# stknx_breakout.net
KiCad netlist of a schematic drawn in EAGLE
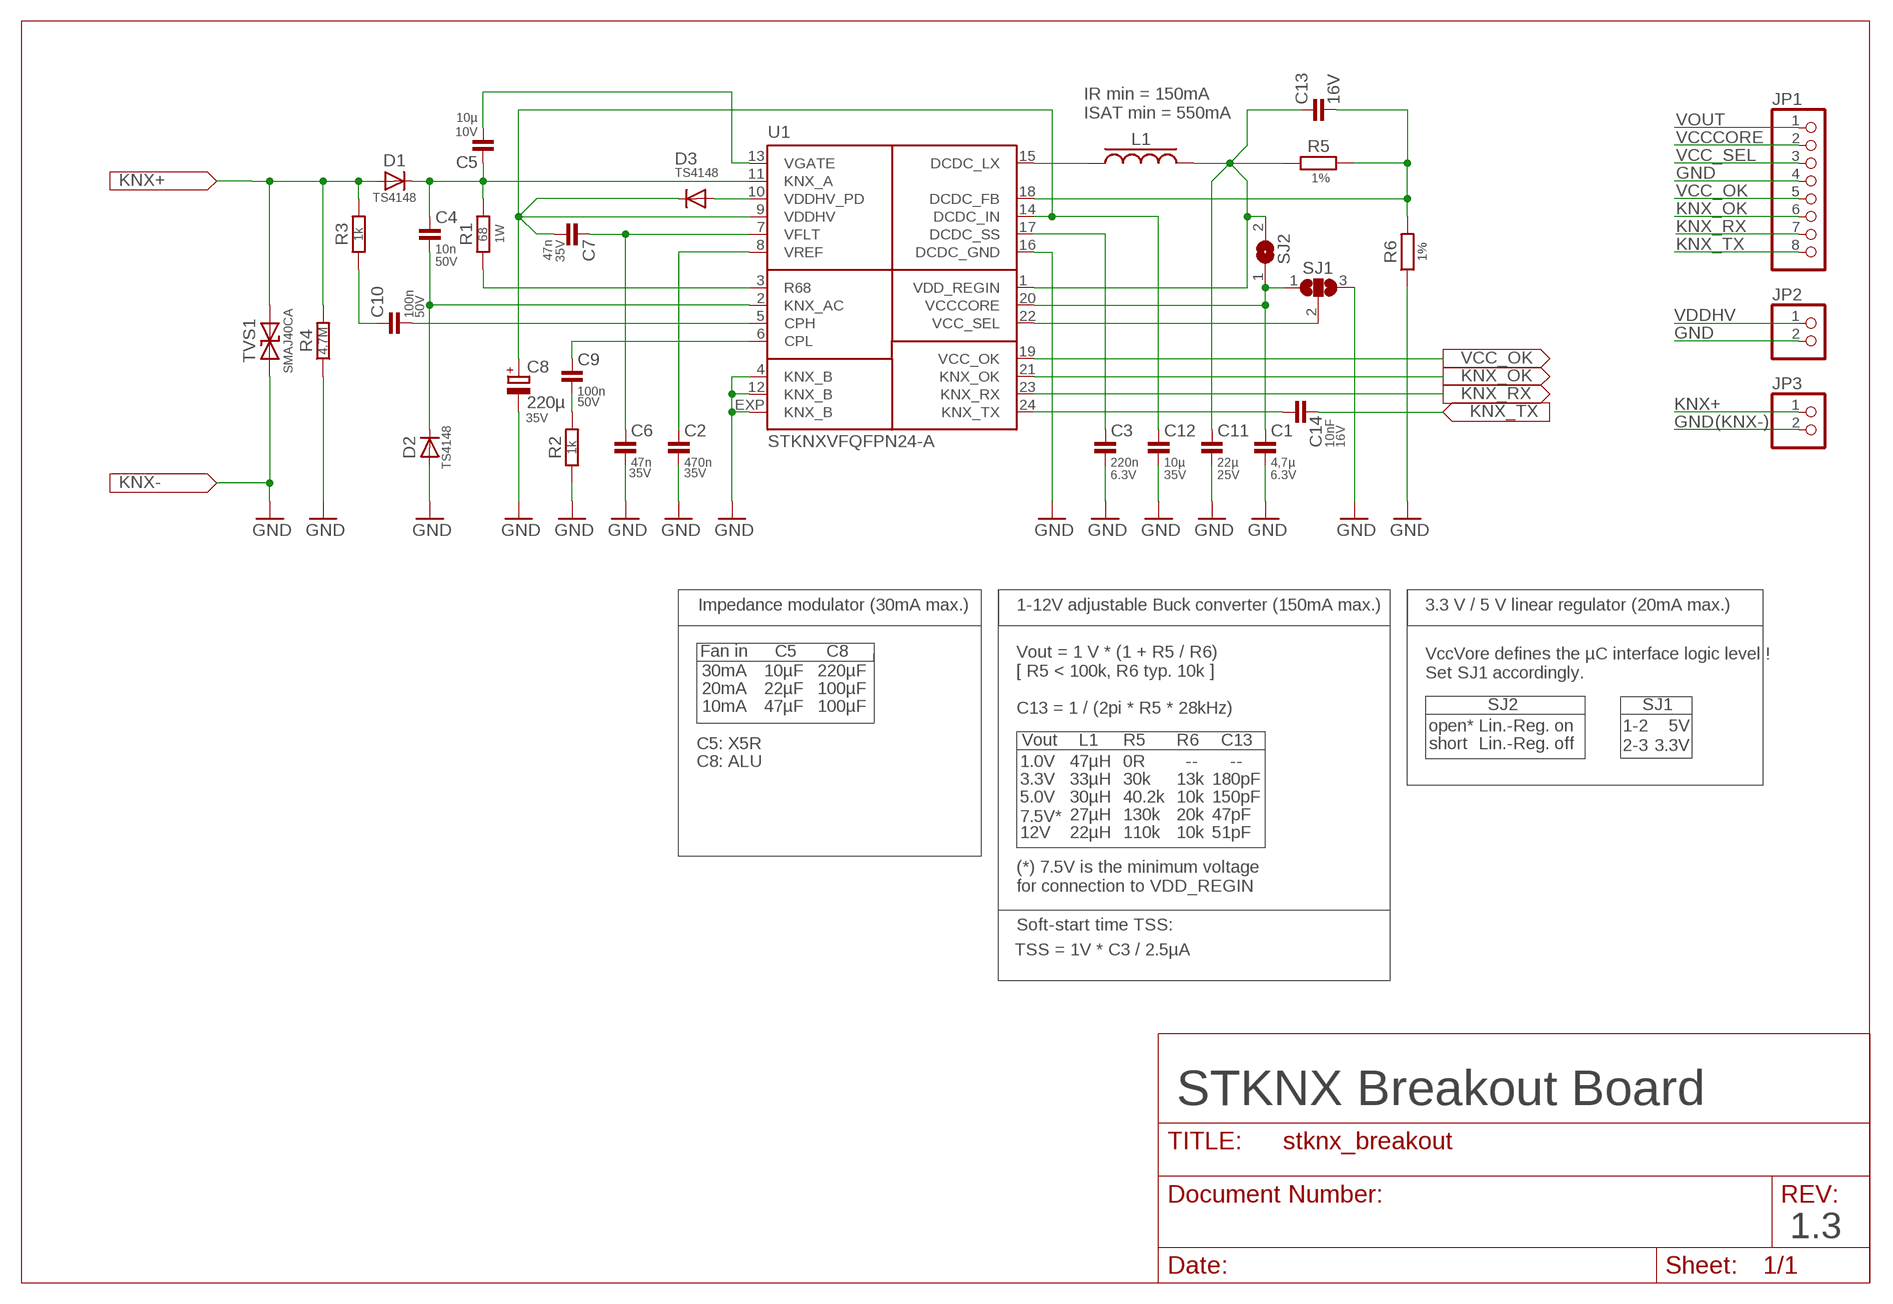
[diagram p0: schematic, sheet 1]

(export (version "E")
  (design (tool "Eeschema 10.0.6"))
  (components
    (comp (ref "C1")
      (value "4,7µ")
      (footprint "eagle-import:C0805")
      (fields (field (name "VOLTAGE") "6.3V"))
      (libsource (lib "eagle-import") (part "C-EUC0805"))
    )
    (comp (ref "C2")
      (value "470n")
      (footprint "eagle-import:C0805")
      (fields (field (name "VOLTAGE") "35V"))
      (libsource (lib "eagle-import") (part "C-EUC0805"))
    )
    (comp (ref "C3")
      (value "220n")
      (footprint "eagle-import:C0805")
      (fields (field (name "VOLTAGE") "6.3V"))
      (libsource (lib "eagle-import") (part "C-EUC0805"))
    )
    (comp (ref "C4")
      (value "10n")
      (footprint "eagle-import:C0805")
      (fields (field (name "VOLTAGE") "50V"))
      (libsource (lib "eagle-import") (part "C-EUC0805"))
    )
    (comp (ref "C5")
      (value "10µ")
      (footprint "eagle-import:C0805")
      (fields (field (name "VOLTAGE") "10V"))
      (libsource (lib "eagle-import") (part "C-EUC0805"))
    )
    (comp (ref "C6")
      (value "47n")
      (footprint "eagle-import:C0805")
      (fields (field (name "VOLTAGE") "35V"))
      (libsource (lib "eagle-import") (part "C-EUC0805"))
    )
    (comp (ref "C7")
      (value "47n")
      (footprint "eagle-import:C0805")
      (fields (field (name "VOLTAGE") "35V"))
      (libsource (lib "eagle-import") (part "C-EUC0805"))
    )
    (comp (ref "C8")
      (value "220µ")
      (footprint "eagle-import:PANASONIC_F")
      (fields (field (name "VOLTAGE") "35V"))
      (libsource (lib "eagle-import") (part "CPOL-EUF"))
    )
    (comp (ref "C9")
      (value "100n")
      (footprint "eagle-import:C0805")
      (fields (field (name "VOLTAGE") "50V"))
      (libsource (lib "eagle-import") (part "C-EUC0805"))
    )
    (comp (ref "C10")
      (value "100n")
      (footprint "eagle-import:C0805")
      (fields (field (name "VOLTAGE") "50V"))
      (libsource (lib "eagle-import") (part "C-EUC0805"))
    )
    (comp (ref "C11")
      (value "22µ")
      (footprint "eagle-import:C0805")
      (fields (field (name "VOLTAGE") "25V"))
      (libsource (lib "eagle-import") (part "C-EUC0805"))
    )
    (comp (ref "C12")
      (value "10µ")
      (footprint "eagle-import:C0805")
      (fields (field (name "VOLTAGE") "35V"))
      (libsource (lib "eagle-import") (part "C-EUC0805"))
    )
    (comp (ref "C13")
      (value "C13")
      (footprint "eagle-import:C0805")
      (fields (field (name "VOLTAGE") "16V"))
      (libsource (lib "eagle-import") (part "C-EUC0805"))
    )
    (comp (ref "C14")
      (value "10nF")
      (footprint "eagle-import:C0805")
      (fields (field (name "VOLTAGE") "16V"))
      (libsource (lib "eagle-import") (part "C-EUC0805"))
    )
    (comp (ref "D1")
      (value "TS4148")
      (footprint "eagle-import:0805")
      (libsource (lib "eagle-import") (part "TS4148"))
    )
    (comp (ref "D2")
      (value "TS4148")
      (footprint "eagle-import:0805")
      (libsource (lib "eagle-import") (part "TS4148"))
    )
    (comp (ref "D3")
      (value "TS4148")
      (footprint "eagle-import:0805")
      (libsource (lib "eagle-import") (part "TS4148"))
    )
    (comp (ref "JP1")
      (value "PINHD-1X8")
      (footprint "eagle-import:1X08")
      (libsource (lib "eagle-import") (part "PINHD-1X8"))
    )
    (comp (ref "JP2")
      (value "PINHD-1X2")
      (footprint "eagle-import:1X02")
      (libsource (lib "eagle-import") (part "PINHD-1X2"))
    )
    (comp (ref "JP3")
      (value "PINHD-1X2")
      (footprint "eagle-import:1X02")
      (libsource (lib "eagle-import") (part "PINHD-1X2"))
    )
    (comp (ref "L1")
      (value "L1")
      (footprint "eagle-import:WE-LQS_4025")
      (libsource (lib "eagle-import") (part "WE-LQS_4025_74404043220A"))
    )
    (comp (ref "R1")
      (value "68")
      (footprint "eagle-import:R1218")
      (libsource (lib "eagle-import") (part "R-EU_R1218"))
    )
    (comp (ref "R2")
      (value "1k")
      (footprint "eagle-import:R0805")
      (libsource (lib "eagle-import") (part "R-EU_R0805"))
    )
    (comp (ref "R3")
      (value "1k")
      (footprint "eagle-import:R0805")
      (libsource (lib "eagle-import") (part "R-EU_R0805"))
    )
    (comp (ref "R4")
      (value "4.7M")
      (footprint "eagle-import:R0805")
      (libsource (lib "eagle-import") (part "R-EU_R0805"))
    )
    (comp (ref "R5")
      (value "R5")
      (footprint "eagle-import:R0805")
      (fields (field (name "TOLERANCE") "1%"))
      (libsource (lib "eagle-import") (part "R-EU_R0805"))
    )
    (comp (ref "R6")
      (value "R6")
      (footprint "eagle-import:R0805")
      (fields (field (name "TOLERANCE") "1%"))
      (libsource (lib "eagle-import") (part "R-EU_R0805"))
    )
    (comp (ref "SJ1")
      (value "SJ2WW")
      (footprint "eagle-import:SJ_2W")
      (libsource (lib "eagle-import") (part "SJ2WW"))
    )
    (comp (ref "SJ2")
      (value "SJW")
      (footprint "eagle-import:SJW")
      (libsource (lib "eagle-import") (part "SJW"))
    )
    (comp (ref "TVS1")
      (value "SMAJ40CA")
      (footprint "eagle-import:DO-214AC(SMA)")
      (libsource (lib "eagle-import") (part "SMAJCA40"))
    )
    (comp (ref "U1")
      (value "STKNXVFQFPN24-A")
      (footprint "eagle-import:VFQFPN24-A")
      (libsource (lib "eagle-import") (part "STKNXVFQFPN24-A"))
    )
  )
  (nets
    (net (code "1") (name "/KNX+") (class "Default")
      (node (ref "D1") (pin "A") (pinfunction "A_A") (pintype "passive"))
      (node (ref "JP3") (pin "1") (pinfunction "1_1") (pintype "passive"))
      (node (ref "R3") (pin "2") (pinfunction "2_2") (pintype "passive"))
      (node (ref "R4") (pin "2") (pinfunction "2_2") (pintype "passive"))
      (node (ref "TVS1") (pin "1") (pinfunction "A1_1") (pintype "passive"))
    )
    (net (code "2") (name "/KNX_OK") (class "Default")
      (node (ref "JP1") (pin "6") (pinfunction "6_6") (pintype "passive"))
      (node (ref "U1") (pin "21") (pinfunction "KNX_OK_21") (pintype "output"))
    )
    (net (code "3") (name "/KNX_RX") (class "Default")
      (node (ref "JP1") (pin "7") (pinfunction "7_7") (pintype "passive"))
      (node (ref "U1") (pin "23") (pinfunction "KNX_RX_23") (pintype "output"))
    )
    (net (code "4") (name "/KNX_TX") (class "Default")
      (node (ref "C14") (pin "2") (pinfunction "2_2") (pintype "passive"))
      (node (ref "JP1") (pin "8") (pinfunction "8_8") (pintype "passive"))
    )
    (net (code "5") (name "/VCCCORE") (class "Default")
      (node (ref "C1") (pin "1") (pinfunction "1_1") (pintype "passive"))
      (node (ref "JP1") (pin "2") (pinfunction "2_2") (pintype "passive"))
      (node (ref "SJ1") (pin "1") (pinfunction "1_1") (pintype "passive"))
      (node (ref "SJ2") (pin "1") (pinfunction "1_1") (pintype "passive"))
      (node (ref "U1") (pin "20") (pinfunction "VCCCORE_20") (pintype "bidirectional"))
    )
    (net (code "6") (name "/VCC_OK") (class "Default")
      (node (ref "JP1") (pin "5") (pinfunction "5_5") (pintype "passive"))
      (node (ref "U1") (pin "19") (pinfunction "VCC_OK_19") (pintype "output"))
    )
    (net (code "7") (name "/VCC_SEL") (class "Default")
      (node (ref "JP1") (pin "3") (pinfunction "3_3") (pintype "passive"))
      (node (ref "SJ1") (pin "2") (pinfunction "2_2") (pintype "passive"))
      (node (ref "U1") (pin "22") (pinfunction "VCC_SEL_22") (pintype "bidirectional"))
    )
    (net (code "8") (name "/VDDHV") (class "Default")
      (node (ref "C12") (pin "1") (pinfunction "1_1") (pintype "passive"))
      (node (ref "C7") (pin "2") (pinfunction "2_2") (pintype "passive"))
      (node (ref "C8") (pin "+") (pinfunction "+_+") (pintype "passive"))
      (node (ref "D3") (pin "C") (pinfunction "C_C") (pintype "passive"))
      (node (ref "JP2") (pin "1") (pinfunction "1_1") (pintype "passive"))
      (node (ref "U1") (pin "14") (pinfunction "DCDC_IN_14") (pintype "bidirectional"))
      (node (ref "U1") (pin "9") (pinfunction "VDDHV_9") (pintype "bidirectional"))
    )
    (net (code "9") (name "/VOUT") (class "Default")
      (node (ref "C11") (pin "1") (pinfunction "1_1") (pintype "passive"))
      (node (ref "C13") (pin "1") (pinfunction "1_1") (pintype "passive"))
      (node (ref "JP1") (pin "1") (pinfunction "1_1") (pintype "passive"))
      (node (ref "L1") (pin "2") (pinfunction "2_2") (pintype "passive"))
      (node (ref "R5") (pin "1") (pinfunction "1_1") (pintype "passive"))
      (node (ref "SJ2") (pin "2") (pinfunction "2_2") (pintype "passive"))
      (node (ref "U1") (pin "1") (pinfunction "VDD_REGIN_1") (pintype "bidirectional"))
    )
    (net (code "10") (name "GND") (class "Default")
      (node (ref "C1") (pin "2") (pinfunction "2_2") (pintype "passive"))
      (node (ref "C11") (pin "2") (pinfunction "2_2") (pintype "passive"))
      (node (ref "C12") (pin "2") (pinfunction "2_2") (pintype "passive"))
      (node (ref "C2") (pin "2") (pinfunction "2_2") (pintype "passive"))
      (node (ref "C3") (pin "2") (pinfunction "2_2") (pintype "passive"))
      (node (ref "C6") (pin "2") (pinfunction "2_2") (pintype "passive"))
      (node (ref "C8") (pin "-") (pinfunction "-_-") (pintype "passive"))
      (node (ref "D2") (pin "A") (pinfunction "A_A") (pintype "passive"))
      (node (ref "JP1") (pin "4") (pinfunction "4_4") (pintype "passive"))
      (node (ref "JP2") (pin "2") (pinfunction "2_2") (pintype "passive"))
      (node (ref "JP3") (pin "2") (pinfunction "2_2") (pintype "passive"))
      (node (ref "R2") (pin "1") (pinfunction "1_1") (pintype "passive"))
      (node (ref "R4") (pin "1") (pinfunction "1_1") (pintype "passive"))
      (node (ref "R6") (pin "1") (pinfunction "1_1") (pintype "passive"))
      (node (ref "SJ1") (pin "3") (pinfunction "3_3") (pintype "passive"))
      (node (ref "TVS1") (pin "2") (pinfunction "A2_2") (pintype "passive"))
      (node (ref "U1") (pin "12") (pinfunction "KNX_B_12") (pintype "power_in"))
      (node (ref "U1") (pin "16") (pinfunction "DCDC_GND_16") (pintype "bidirectional"))
      (node (ref "U1") (pin "4") (pinfunction "KNX_B_4") (pintype "power_in"))
      (node (ref "U1") (pin "EXP") (pinfunction "KNX_B_EXP") (pintype "power_in"))
    )
    (net (code "11") (name "Net-(C9-Pad2)") (class "Default")
      (node (ref "C9") (pin "2") (pinfunction "2_2") (pintype "passive"))
      (node (ref "R2") (pin "2") (pinfunction "2_2") (pintype "passive"))
    )
    (net (code "12") (name "Net-(C10-Pad1)") (class "Default")
      (node (ref "C10") (pin "1") (pinfunction "1_1") (pintype "passive"))
      (node (ref "R3") (pin "1") (pinfunction "1_1") (pintype "passive"))
    )
    (net (code "13") (name "Net-(U1-CPH)") (class "Default")
      (node (ref "C10") (pin "2") (pinfunction "2_2") (pintype "passive"))
      (node (ref "U1") (pin "5") (pinfunction "CPH_5") (pintype "bidirectional"))
    )
    (net (code "14") (name "Net-(U1-CPL)") (class "Default")
      (node (ref "C9") (pin "1") (pinfunction "1_1") (pintype "passive"))
      (node (ref "U1") (pin "6") (pinfunction "CPL_6") (pintype "bidirectional"))
    )
    (net (code "15") (name "Net-(U1-DCDC_FB)") (class "Default")
      (node (ref "C13") (pin "2") (pinfunction "2_2") (pintype "passive"))
      (node (ref "R5") (pin "2") (pinfunction "2_2") (pintype "passive"))
      (node (ref "R6") (pin "2") (pinfunction "2_2") (pintype "passive"))
      (node (ref "U1") (pin "18") (pinfunction "DCDC_FB_18") (pintype "bidirectional"))
    )
    (net (code "16") (name "Net-(U1-DCDC_LX)") (class "Default")
      (node (ref "L1") (pin "1") (pinfunction "1_1") (pintype "passive"))
      (node (ref "U1") (pin "15") (pinfunction "DCDC_LX_15") (pintype "bidirectional"))
    )
    (net (code "17") (name "Net-(U1-DCDC_SS)") (class "Default")
      (node (ref "C3") (pin "1") (pinfunction "1_1") (pintype "passive"))
      (node (ref "U1") (pin "17") (pinfunction "DCDC_SS_17") (pintype "bidirectional"))
    )
    (net (code "18") (name "Net-(U1-KNX_A)") (class "Default")
      (node (ref "C4") (pin "1") (pinfunction "1_1") (pintype "passive"))
      (node (ref "C5") (pin "1") (pinfunction "1_1") (pintype "passive"))
      (node (ref "D1") (pin "C") (pinfunction "C_C") (pintype "passive"))
      (node (ref "R1") (pin "2") (pinfunction "2_2") (pintype "passive"))
      (node (ref "U1") (pin "11") (pinfunction "KNX_A_11") (pintype "bidirectional"))
    )
    (net (code "19") (name "Net-(U1-KNX_AC)") (class "Default")
      (node (ref "C4") (pin "2") (pinfunction "2_2") (pintype "passive"))
      (node (ref "D2") (pin "C") (pinfunction "C_C") (pintype "passive"))
      (node (ref "U1") (pin "2") (pinfunction "KNX_AC_2") (pintype "bidirectional"))
    )
    (net (code "20") (name "Net-(U1-KNX_TX)") (class "Default")
      (node (ref "C14") (pin "1") (pinfunction "1_1") (pintype "passive"))
      (node (ref "U1") (pin "24") (pinfunction "KNX_TX_24") (pintype "input"))
    )
    (net (code "21") (name "Net-(U1-R68)") (class "Default")
      (node (ref "R1") (pin "1") (pinfunction "1_1") (pintype "passive"))
      (node (ref "U1") (pin "3") (pinfunction "R68_3") (pintype "bidirectional"))
    )
    (net (code "22") (name "Net-(U1-VDDHV_PD)") (class "Default")
      (node (ref "D3") (pin "A") (pinfunction "A_A") (pintype "passive"))
      (node (ref "U1") (pin "10") (pinfunction "VDDHV_PD_10") (pintype "bidirectional"))
    )
    (net (code "23") (name "Net-(U1-VFLT)") (class "Default")
      (node (ref "C6") (pin "1") (pinfunction "1_1") (pintype "passive"))
      (node (ref "C7") (pin "1") (pinfunction "1_1") (pintype "passive"))
      (node (ref "U1") (pin "7") (pinfunction "VFLT_7") (pintype "bidirectional"))
    )
    (net (code "24") (name "Net-(U1-VGATE)") (class "Default")
      (node (ref "C5") (pin "2") (pinfunction "2_2") (pintype "passive"))
      (node (ref "U1") (pin "13") (pinfunction "VGATE_13") (pintype "bidirectional"))
    )
    (net (code "25") (name "Net-(U1-VREF)") (class "Default")
      (node (ref "C2") (pin "1") (pinfunction "1_1") (pintype "passive"))
      (node (ref "U1") (pin "8") (pinfunction "VREF_8") (pintype "bidirectional"))
    )
  )
)
